# Main.net
KiCad netlist of a schematic drawn in Altium Designer
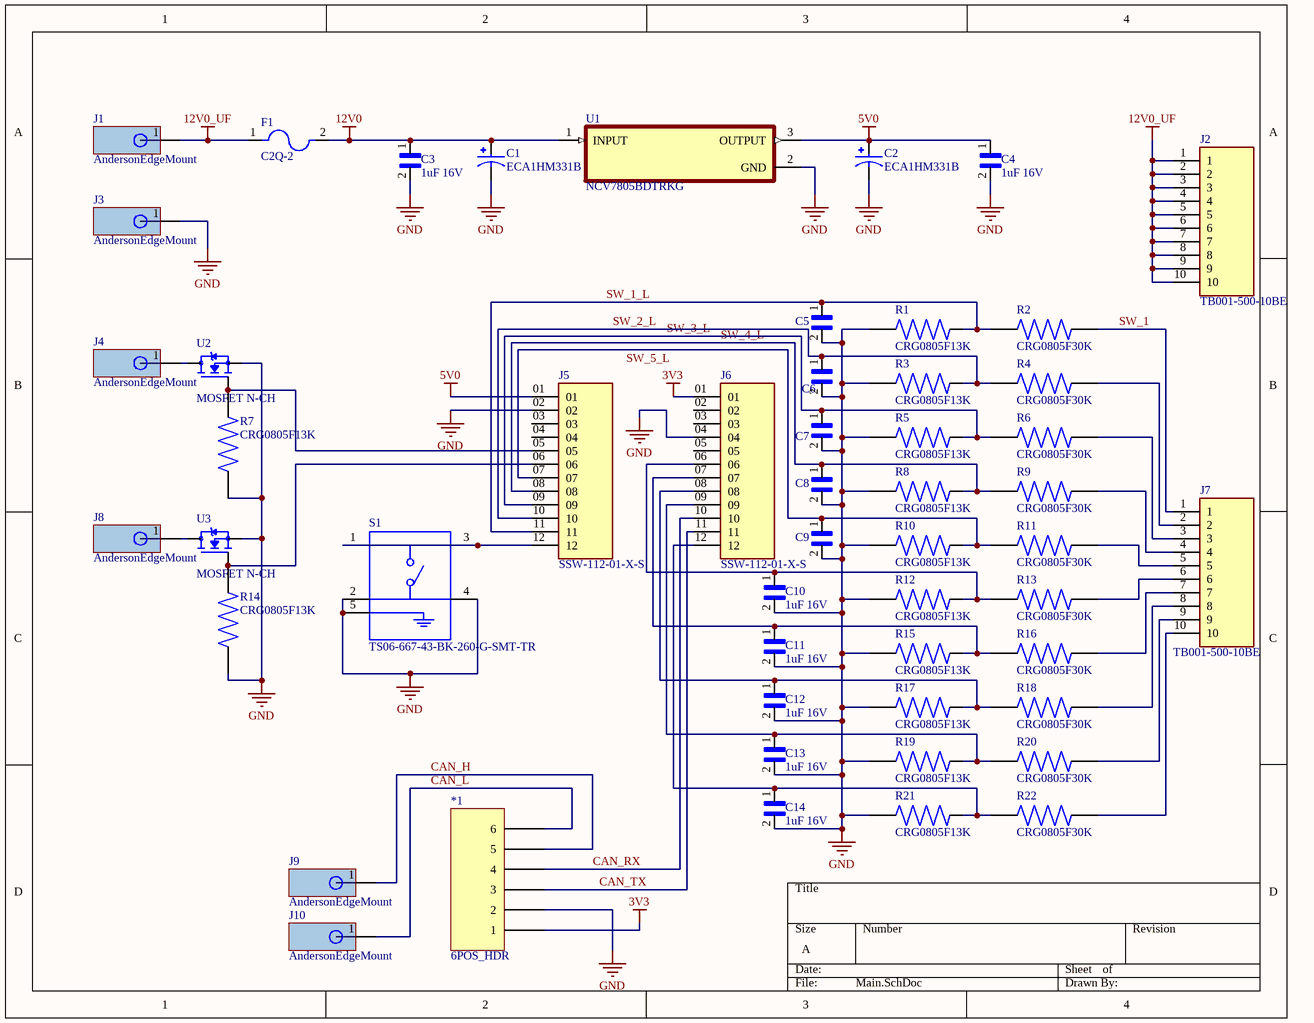
[diagram p0: Main.SchDoc]

(export (version "E")
  (design (tool "Eeschema 10.0.6"))
  (components
    (comp (ref "*1") (value "6POS_HDR") (footprint "6POS_HDR") (libsource (lib "MainLib") (part "6POS_HDR")))
    (comp (ref "C1")
      (value "ECA1HM331B")
      (footprint "CAPPRD500W60D1000H1600")
      (description "M-A")
      (fields (field (name "MF") "{'manufacturer': u'Panasonic Electronic'}"))
      (libsource (lib "SnapEDA_Library") (part "ECA1HM331B"))
    )
    (comp (ref "C2")
      (value "ECA1HM331B")
      (footprint "CAPPRD500W60D1000H1600")
      (description "M-A")
      (fields (field (name "MF") "{'manufacturer': u'Panasonic Electronic'}"))
      (libsource (lib "SnapEDA_Library") (part "ECA1HM331B"))
    )
    (comp (ref "C3")
      (value "1uF 16V")
      (footprint "CAPC2012X135N")
      (description "Cap Ceramic 1uF 16V X7R 10% Pad SMD 0805 125C T/R")
      (fields
        (field (name "MP") "CL21B105KOFNNNE")
        (field (name "MF") "{'manufacturer': u'Samsung Electro-Mechanics'}")
      )
      (libsource (lib "MCU_Lib") (part "CL21B105KOFNNNE"))
    )
    (comp (ref "C4")
      (value "1uF 16V")
      (footprint "CAPC2012X135N")
      (description "Cap Ceramic 1uF 16V X7R 10% Pad SMD 0805 125C T/R")
      (fields
        (field (name "MP") "CL21B105KOFNNNE")
        (field (name "MF") "{'manufacturer': u'Samsung Electro-Mechanics'}")
      )
      (libsource (lib "MCU_Lib") (part "CL21B105KOFNNNE"))
    )
    (comp (ref "C5")
      (value "1uF 16V")
      (footprint "CAPC2012X135N")
      (description "Cap Ceramic 1uF 16V X7R 10% Pad SMD 0805 125C T/R")
      (fields
        (field (name "MP") "CL21B105KOFNNNE")
        (field (name "MF") "{'manufacturer': u'Samsung Electro-Mechanics'}")
      )
      (libsource (lib "MCU_Lib") (part "CL21B105KOFNNNE"))
    )
    (comp (ref "C6")
      (value "1uF 16V")
      (footprint "CAPC2012X135N")
      (description "Cap Ceramic 1uF 16V X7R 10% Pad SMD 0805 125C T/R")
      (fields
        (field (name "MP") "CL21B105KOFNNNE")
        (field (name "MF") "{'manufacturer': u'Samsung Electro-Mechanics'}")
      )
      (libsource (lib "MCU_Lib") (part "CL21B105KOFNNNE"))
    )
    (comp (ref "C7")
      (value "1uF 16V")
      (footprint "CAPC2012X135N")
      (description "Cap Ceramic 1uF 16V X7R 10% Pad SMD 0805 125C T/R")
      (fields
        (field (name "MP") "CL21B105KOFNNNE")
        (field (name "MF") "{'manufacturer': u'Samsung Electro-Mechanics'}")
      )
      (libsource (lib "MCU_Lib") (part "CL21B105KOFNNNE"))
    )
    (comp (ref "C8")
      (value "1uF 16V")
      (footprint "CAPC2012X135N")
      (description "Cap Ceramic 1uF 16V X7R 10% Pad SMD 0805 125C T/R")
      (fields
        (field (name "MP") "CL21B105KOFNNNE")
        (field (name "MF") "{'manufacturer': u'Samsung Electro-Mechanics'}")
      )
      (libsource (lib "MCU_Lib") (part "CL21B105KOFNNNE"))
    )
    (comp (ref "C9")
      (value "1uF 16V")
      (footprint "CAPC2012X135N")
      (description "Cap Ceramic 1uF 16V X7R 10% Pad SMD 0805 125C T/R")
      (fields
        (field (name "MP") "CL21B105KOFNNNE")
        (field (name "MF") "{'manufacturer': u'Samsung Electro-Mechanics'}")
      )
      (libsource (lib "MCU_Lib") (part "CL21B105KOFNNNE"))
    )
    (comp (ref "C10")
      (value "1uF 16V")
      (footprint "CAPC2012X135N")
      (description "Cap Ceramic 1uF 16V X7R 10% Pad SMD 0805 125C T/R")
      (fields
        (field (name "MP") "CL21B105KOFNNNE")
        (field (name "MF") "{'manufacturer': u'Samsung Electro-Mechanics'}")
      )
      (libsource (lib "MCU_Lib") (part "CL21B105KOFNNNE"))
    )
    (comp (ref "C11")
      (value "1uF 16V")
      (footprint "CAPC2012X135N")
      (description "Cap Ceramic 1uF 16V X7R 10% Pad SMD 0805 125C T/R")
      (fields
        (field (name "MP") "CL21B105KOFNNNE")
        (field (name "MF") "{'manufacturer': u'Samsung Electro-Mechanics'}")
      )
      (libsource (lib "MCU_Lib") (part "CL21B105KOFNNNE"))
    )
    (comp (ref "C12")
      (value "1uF 16V")
      (footprint "CAPC2012X135N")
      (description "Cap Ceramic 1uF 16V X7R 10% Pad SMD 0805 125C T/R")
      (fields
        (field (name "MP") "CL21B105KOFNNNE")
        (field (name "MF") "{'manufacturer': u'Samsung Electro-Mechanics'}")
      )
      (libsource (lib "MCU_Lib") (part "CL21B105KOFNNNE"))
    )
    (comp (ref "C13")
      (value "1uF 16V")
      (footprint "CAPC2012X135N")
      (description "Cap Ceramic 1uF 16V X7R 10% Pad SMD 0805 125C T/R")
      (fields
        (field (name "MP") "CL21B105KOFNNNE")
        (field (name "MF") "{'manufacturer': u'Samsung Electro-Mechanics'}")
      )
      (libsource (lib "MCU_Lib") (part "CL21B105KOFNNNE"))
    )
    (comp (ref "C14")
      (value "1uF 16V")
      (footprint "CAPC2012X135N")
      (description "Cap Ceramic 1uF 16V X7R 10% Pad SMD 0805 125C T/R")
      (fields
        (field (name "MP") "CL21B105KOFNNNE")
        (field (name "MF") "{'manufacturer': u'Samsung Electro-Mechanics'}")
      )
      (libsource (lib "MCU_Lib") (part "CL21B105KOFNNNE"))
    )
    (comp (ref "F1")
      (value "C2Q-2")
      (footprint "FUSC1608X56N")
      (fields (field (name "MF") "{'manufacturer': u'Bel Fuse'}"))
      (libsource (lib "SnapEDA_Library") (part "C2Q-2"))
    )
    (comp (ref "J1")
      (value "AndersonEdgeMount")
      (footprint "AndersonEdgeMount")
      (description "Edge Mounted Anderson Connector")
      (libsource (lib "MainLib") (part "AndersonEdgeMount"))
    )
    (comp (ref "J2")
      (value "TB001-500-10BE")
      (footprint "CUI_TB001-500-10BE")
      (fields (field (name "MF") "{'manufacturer': u'CUI Devices'}"))
      (libsource (lib "SnapEDA_Library") (part "TB001-500-10BE"))
    )
    (comp (ref "J3")
      (value "AndersonEdgeMount")
      (footprint "AndersonEdgeMount")
      (description "Edge Mounted Anderson Connector")
      (libsource (lib "MainLib") (part "AndersonEdgeMount"))
    )
    (comp (ref "J4")
      (value "AndersonEdgeMount")
      (footprint "AndersonEdgeMount")
      (description "Edge Mounted Anderson Connector")
      (libsource (lib "MainLib") (part "AndersonEdgeMount"))
    )
    (comp (ref "J5")
      (value "SSW-112-01-X-S")
      (footprint "SAMTEC_SSW-112-01-X-S")
      (description "CONN RCPT 12POS 0.1 GOLD PCB")
      (fields (field (name "MF") "{'manufacturer': u'Samtec'}"))
      (libsource (lib "SnapEDA_Library") (part "SSW-112-01-X-S"))
    )
    (comp (ref "J6")
      (value "SSW-112-01-X-S")
      (footprint "SAMTEC_SSW-112-01-X-S")
      (description "CONN RCPT 12POS 0.1 GOLD PCB")
      (fields (field (name "MF") "{'manufacturer': u'Samtec'}"))
      (libsource (lib "SnapEDA_Library") (part "SSW-112-01-X-S"))
    )
    (comp (ref "J7")
      (value "TB001-500-10BE")
      (footprint "CUI_TB001-500-10BE")
      (fields (field (name "MF") "{'manufacturer': u'CUI Devices'}"))
      (libsource (lib "SnapEDA_Library") (part "TB001-500-10BE"))
    )
    (comp (ref "J8")
      (value "AndersonEdgeMount")
      (footprint "AndersonEdgeMount")
      (description "Edge Mounted Anderson Connector")
      (libsource (lib "MainLib") (part "AndersonEdgeMount"))
    )
    (comp (ref "J9")
      (value "AndersonEdgeMount")
      (footprint "AndersonEdgeMount")
      (description "Edge Mounted Anderson Connector")
      (libsource (lib "MainLib") (part "AndersonEdgeMount"))
    )
    (comp (ref "J10")
      (value "AndersonEdgeMount")
      (footprint "AndersonEdgeMount")
      (description "Edge Mounted Anderson Connector")
      (libsource (lib "MainLib") (part "AndersonEdgeMount"))
    )
    (comp (ref "R1")
      (value "CRG0805F13K")
      (footprint "RESC2012X65N")
      (description "CRG0805 1% 13K")
      (fields (field (name "MF") "{'manufacturer': u'TE Connectivity'}"))
      (libsource (lib "SnapEDA_Library") (part "CRG0805F13K"))
    )
    (comp (ref "R2")
      (value "CRG0805F30K")
      (footprint "RESC2012X65N")
      (description "CRG0805 1% 30K")
      (fields (field (name "MF") "{'manufacturer': u'TE Connectivity'}"))
      (libsource (lib "SnapEDA_Library") (part "CRG0805F30K"))
    )
    (comp (ref "R3")
      (value "CRG0805F13K")
      (footprint "RESC2012X65N")
      (description "CRG0805 1% 13K")
      (fields (field (name "MF") "{'manufacturer': u'TE Connectivity'}"))
      (libsource (lib "SnapEDA_Library") (part "CRG0805F13K"))
    )
    (comp (ref "R4")
      (value "CRG0805F30K")
      (footprint "RESC2012X65N")
      (description "CRG0805 1% 30K")
      (fields (field (name "MF") "{'manufacturer': u'TE Connectivity'}"))
      (libsource (lib "SnapEDA_Library") (part "CRG0805F30K"))
    )
    (comp (ref "R5")
      (value "CRG0805F13K")
      (footprint "RESC2012X65N")
      (description "CRG0805 1% 13K")
      (fields (field (name "MF") "{'manufacturer': u'TE Connectivity'}"))
      (libsource (lib "SnapEDA_Library") (part "CRG0805F13K"))
    )
    (comp (ref "R6")
      (value "CRG0805F30K")
      (footprint "RESC2012X65N")
      (description "CRG0805 1% 30K")
      (fields (field (name "MF") "{'manufacturer': u'TE Connectivity'}"))
      (libsource (lib "SnapEDA_Library") (part "CRG0805F30K"))
    )
    (comp (ref "R7")
      (value "CRG0805F13K")
      (footprint "RESC2012X65N")
      (description "CRG0805 1% 13K")
      (fields (field (name "MF") "{'manufacturer': u'TE Connectivity'}"))
      (libsource (lib "SnapEDA_Library") (part "CRG0805F13K"))
    )
    (comp (ref "R8")
      (value "CRG0805F13K")
      (footprint "RESC2012X65N")
      (description "CRG0805 1% 13K")
      (fields (field (name "MF") "{'manufacturer': u'TE Connectivity'}"))
      (libsource (lib "SnapEDA_Library") (part "CRG0805F13K"))
    )
    (comp (ref "R9")
      (value "CRG0805F30K")
      (footprint "RESC2012X65N")
      (description "CRG0805 1% 30K")
      (fields (field (name "MF") "{'manufacturer': u'TE Connectivity'}"))
      (libsource (lib "SnapEDA_Library") (part "CRG0805F30K"))
    )
    (comp (ref "R10")
      (value "CRG0805F13K")
      (footprint "RESC2012X65N")
      (description "CRG0805 1% 13K")
      (fields (field (name "MF") "{'manufacturer': u'TE Connectivity'}"))
      (libsource (lib "SnapEDA_Library") (part "CRG0805F13K"))
    )
    (comp (ref "R11")
      (value "CRG0805F30K")
      (footprint "RESC2012X65N")
      (description "CRG0805 1% 30K")
      (fields (field (name "MF") "{'manufacturer': u'TE Connectivity'}"))
      (libsource (lib "SnapEDA_Library") (part "CRG0805F30K"))
    )
    (comp (ref "R12")
      (value "CRG0805F13K")
      (footprint "RESC2012X65N")
      (description "CRG0805 1% 13K")
      (fields (field (name "MF") "{'manufacturer': u'TE Connectivity'}"))
      (libsource (lib "SnapEDA_Library") (part "CRG0805F13K"))
    )
    (comp (ref "R13")
      (value "CRG0805F30K")
      (footprint "RESC2012X65N")
      (description "CRG0805 1% 30K")
      (fields (field (name "MF") "{'manufacturer': u'TE Connectivity'}"))
      (libsource (lib "SnapEDA_Library") (part "CRG0805F30K"))
    )
    (comp (ref "R14")
      (value "CRG0805F13K")
      (footprint "RESC2012X65N")
      (description "CRG0805 1% 13K")
      (fields (field (name "MF") "{'manufacturer': u'TE Connectivity'}"))
      (libsource (lib "SnapEDA_Library") (part "CRG0805F13K"))
    )
    (comp (ref "R15")
      (value "CRG0805F13K")
      (footprint "RESC2012X65N")
      (description "CRG0805 1% 13K")
      (fields (field (name "MF") "{'manufacturer': u'TE Connectivity'}"))
      (libsource (lib "SnapEDA_Library") (part "CRG0805F13K"))
    )
    (comp (ref "R16")
      (value "CRG0805F30K")
      (footprint "RESC2012X65N")
      (description "CRG0805 1% 30K")
      (fields (field (name "MF") "{'manufacturer': u'TE Connectivity'}"))
      (libsource (lib "SnapEDA_Library") (part "CRG0805F30K"))
    )
    (comp (ref "R17")
      (value "CRG0805F13K")
      (footprint "RESC2012X65N")
      (description "CRG0805 1% 13K")
      (fields (field (name "MF") "{'manufacturer': u'TE Connectivity'}"))
      (libsource (lib "SnapEDA_Library") (part "CRG0805F13K"))
    )
    (comp (ref "R18")
      (value "CRG0805F30K")
      (footprint "RESC2012X65N")
      (description "CRG0805 1% 30K")
      (fields (field (name "MF") "{'manufacturer': u'TE Connectivity'}"))
      (libsource (lib "SnapEDA_Library") (part "CRG0805F30K"))
    )
    (comp (ref "R19")
      (value "CRG0805F13K")
      (footprint "RESC2012X65N")
      (description "CRG0805 1% 13K")
      (fields (field (name "MF") "{'manufacturer': u'TE Connectivity'}"))
      (libsource (lib "SnapEDA_Library") (part "CRG0805F13K"))
    )
    (comp (ref "R20")
      (value "CRG0805F30K")
      (footprint "RESC2012X65N")
      (description "CRG0805 1% 30K")
      (fields (field (name "MF") "{'manufacturer': u'TE Connectivity'}"))
      (libsource (lib "SnapEDA_Library") (part "CRG0805F30K"))
    )
    (comp (ref "R21")
      (value "CRG0805F13K")
      (footprint "RESC2012X65N")
      (description "CRG0805 1% 13K")
      (fields (field (name "MF") "{'manufacturer': u'TE Connectivity'}"))
      (libsource (lib "SnapEDA_Library") (part "CRG0805F13K"))
    )
    (comp (ref "R22")
      (value "CRG0805F30K")
      (footprint "RESC2012X65N")
      (description "CRG0805 1% 30K")
      (fields (field (name "MF") "{'manufacturer': u'TE Connectivity'}"))
      (libsource (lib "SnapEDA_Library") (part "CRG0805F30K"))
    )
    (comp (ref "S1")
      (value "TS06-667-43-BK-260-G-SMT-TR")
      (footprint "SW_TS06-667-43-BK-260-G-SMT-TR")
      (fields (field (name "MF") "{'manufacturer': u'CUI Devices'}"))
      (libsource (lib "SnapEDA_Library") (part "TS06-667-43-BK-260-G-SMT-TR"))
    )
    (comp (ref "U1")
      (value "NCV7805BDTRKG")
      (footprint "DPAK229P990X238-4N")
      (fields (field (name "MF") "{'manufacturer': u'ON Semiconductor'}"))
      (libsource (lib "SnapEDA_Library") (part "NCV7805BDTRKG"))
    )
    (comp (ref "U2")
      (value "MOSFET N-CH")
      (footprint "ZXMN6A09GTA")
      (libsource (lib "MainLib") (part "ZXMN6A09GTA"))
    )
    (comp (ref "U3")
      (value "MOSFET N-CH")
      (footprint "ZXMN6A09GTA")
      (libsource (lib "MainLib") (part "ZXMN6A09GTA"))
    )
  )
  (nets
    (net (code "1") (name "/CAN_H") (class "Default")
      (node (ref "*1") (pin "5") (pinfunction "5_5") (pintype "passive"))
      (node (ref "J9") (pin "1") (pinfunction "1_1") (pintype "passive"))
    )
    (net (code "2") (name "/CAN_L") (class "Default")
      (node (ref "*1") (pin "6") (pinfunction "6_6") (pintype "passive"))
      (node (ref "J10") (pin "1") (pinfunction "1_1") (pintype "passive"))
    )
    (net (code "3") (name "/CAN_RX") (class "Default")
      (node (ref "*1") (pin "4") (pinfunction "4_4") (pintype "passive"))
      (node (ref "J6") (pin "10") (pinfunction "10_10") (pintype "passive"))
    )
    (net (code "4") (name "/CAN_TX") (class "Default")
      (node (ref "*1") (pin "3") (pinfunction "3_3") (pintype "passive"))
      (node (ref "J6") (pin "11") (pinfunction "11_11") (pintype "passive"))
    )
    (net (code "5") (name "/SW_1") (class "Default")
      (node (ref "J7") (pin "1") (pinfunction "1_1") (pintype "passive"))
      (node (ref "R2") (pin "2") (pinfunction "2_2") (pintype "passive"))
    )
    (net (code "6") (name "/SW_1_L") (class "Default")
      (node (ref "C5") (pin "1") (pinfunction "1_1") (pintype "passive"))
      (node (ref "J5") (pin "11") (pinfunction "11_11") (pintype "passive"))
      (node (ref "R1") (pin "1") (pinfunction "1_1") (pintype "passive"))
      (node (ref "R2") (pin "1") (pinfunction "1_1") (pintype "passive"))
    )
    (net (code "7") (name "/SW_2_L") (class "Default")
      (node (ref "C6") (pin "1") (pinfunction "1_1") (pintype "passive"))
      (node (ref "J5") (pin "10") (pinfunction "10_10") (pintype "passive"))
      (node (ref "R3") (pin "1") (pinfunction "1_1") (pintype "passive"))
      (node (ref "R4") (pin "1") (pinfunction "1_1") (pintype "passive"))
    )
    (net (code "8") (name "/SW_3_L") (class "Default")
      (node (ref "C7") (pin "1") (pinfunction "1_1") (pintype "passive"))
      (node (ref "J5") (pin "09") (pinfunction "09_09") (pintype "passive"))
      (node (ref "R5") (pin "1") (pinfunction "1_1") (pintype "passive"))
      (node (ref "R6") (pin "1") (pinfunction "1_1") (pintype "passive"))
    )
    (net (code "9") (name "/SW_4_L") (class "Default")
      (node (ref "C8") (pin "1") (pinfunction "1_1") (pintype "passive"))
      (node (ref "J5") (pin "08") (pinfunction "08_08") (pintype "passive"))
      (node (ref "R8") (pin "1") (pinfunction "1_1") (pintype "passive"))
      (node (ref "R9") (pin "1") (pinfunction "1_1") (pintype "passive"))
    )
    (net (code "10") (name "/SW_5_L") (class "Default")
      (node (ref "C9") (pin "1") (pinfunction "1_1") (pintype "passive"))
      (node (ref "J5") (pin "07") (pinfunction "07_07") (pintype "passive"))
      (node (ref "R10") (pin "1") (pinfunction "1_1") (pintype "passive"))
      (node (ref "R11") (pin "1") (pinfunction "1_1") (pintype "passive"))
    )
    (net (code "11") (name "3V3") (class "Default")
      (node (ref "*1") (pin "1") (pinfunction "1_1") (pintype "passive"))
      (node (ref "J6") (pin "01") (pinfunction "01_01") (pintype "passive"))
    )
    (net (code "12") (name "5V0") (class "Default")
      (node (ref "C2") (pin "P") (pinfunction "P_P") (pintype "passive"))
      (node (ref "C4") (pin "1") (pinfunction "1_1") (pintype "passive"))
      (node (ref "J5") (pin "01") (pinfunction "01_01") (pintype "passive"))
      (node (ref "U1") (pin "3") (pinfunction "OUTPUT_3") (pintype "output"))
    )
    (net (code "13") (name "12V0") (class "Default")
      (node (ref "C1") (pin "P") (pinfunction "P_P") (pintype "passive"))
      (node (ref "C3") (pin "1") (pinfunction "1_1") (pintype "passive"))
      (node (ref "F1") (pin "2") (pinfunction "2_2") (pintype "passive"))
      (node (ref "U1") (pin "1") (pinfunction "INPUT_1") (pintype "input"))
    )
    (net (code "14") (name "12V0_UF") (class "Default")
      (node (ref "F1") (pin "1") (pinfunction "1_1") (pintype "passive"))
      (node (ref "J1") (pin "1") (pinfunction "1_1") (pintype "passive"))
      (node (ref "J2") (pin "1") (pinfunction "1_1") (pintype "passive"))
      (node (ref "J2") (pin "10") (pinfunction "10_10") (pintype "passive"))
      (node (ref "J2") (pin "2") (pinfunction "2_2") (pintype "passive"))
      (node (ref "J2") (pin "3") (pinfunction "3_3") (pintype "passive"))
      (node (ref "J2") (pin "4") (pinfunction "4_4") (pintype "passive"))
      (node (ref "J2") (pin "5") (pinfunction "5_5") (pintype "passive"))
      (node (ref "J2") (pin "6") (pinfunction "6_6") (pintype "passive"))
      (node (ref "J2") (pin "7") (pinfunction "7_7") (pintype "passive"))
      (node (ref "J2") (pin "8") (pinfunction "8_8") (pintype "passive"))
      (node (ref "J2") (pin "9") (pinfunction "9_9") (pintype "passive"))
    )
    (net (code "15") (name "GND") (class "Default")
      (node (ref "*1") (pin "2") (pinfunction "2_2") (pintype "passive"))
      (node (ref "C1") (pin "N") (pinfunction "N_N") (pintype "passive"))
      (node (ref "C10") (pin "2") (pinfunction "2_2") (pintype "passive"))
      (node (ref "C11") (pin "2") (pinfunction "2_2") (pintype "passive"))
      (node (ref "C12") (pin "2") (pinfunction "2_2") (pintype "passive"))
      (node (ref "C13") (pin "2") (pinfunction "2_2") (pintype "passive"))
      (node (ref "C14") (pin "2") (pinfunction "2_2") (pintype "passive"))
      (node (ref "C2") (pin "N") (pinfunction "N_N") (pintype "passive"))
      (node (ref "C3") (pin "2") (pinfunction "2_2") (pintype "passive"))
      (node (ref "C4") (pin "2") (pinfunction "2_2") (pintype "passive"))
      (node (ref "C5") (pin "2") (pinfunction "2_2") (pintype "passive"))
      (node (ref "C6") (pin "2") (pinfunction "2_2") (pintype "passive"))
      (node (ref "C7") (pin "2") (pinfunction "2_2") (pintype "passive"))
      (node (ref "C8") (pin "2") (pinfunction "2_2") (pintype "passive"))
      (node (ref "C9") (pin "2") (pinfunction "2_2") (pintype "passive"))
      (node (ref "J3") (pin "1") (pinfunction "1_1") (pintype "passive"))
      (node (ref "J5") (pin "02") (pinfunction "02_02") (pintype "passive"))
      (node (ref "J6") (pin "04") (pinfunction "04_04") (pintype "passive"))
      (node (ref "R1") (pin "2") (pinfunction "2_2") (pintype "passive"))
      (node (ref "R10") (pin "2") (pinfunction "2_2") (pintype "passive"))
      (node (ref "R12") (pin "2") (pinfunction "2_2") (pintype "passive"))
      (node (ref "R14") (pin "1") (pinfunction "1_1") (pintype "passive"))
      (node (ref "R15") (pin "2") (pinfunction "2_2") (pintype "passive"))
      (node (ref "R17") (pin "2") (pinfunction "2_2") (pintype "passive"))
      (node (ref "R19") (pin "2") (pinfunction "2_2") (pintype "passive"))
      (node (ref "R21") (pin "2") (pinfunction "2_2") (pintype "passive"))
      (node (ref "R3") (pin "2") (pinfunction "2_2") (pintype "passive"))
      (node (ref "R5") (pin "2") (pinfunction "2_2") (pintype "passive"))
      (node (ref "R7") (pin "1") (pinfunction "1_1") (pintype "passive"))
      (node (ref "R8") (pin "2") (pinfunction "2_2") (pintype "passive"))
      (node (ref "S1") (pin "2") (pinfunction "2_2") (pintype "passive"))
      (node (ref "S1") (pin "4") (pinfunction "4_4") (pintype "passive"))
      (node (ref "S1") (pin "5") (pinfunction "5_5") (pintype "passive"))
      (node (ref "U1") (pin "2") (pinfunction "GND_2") (pintype "power_in"))
      (node (ref "U2") (pin "3") (pinfunction "3_3") (pintype "passive"))
      (node (ref "U3") (pin "3") (pinfunction "3_3") (pintype "passive"))
    )
    (net (code "16") (name "Net-(C10-Pad1)") (class "Default")
      (node (ref "C10") (pin "1") (pinfunction "1_1") (pintype "passive"))
      (node (ref "J6") (pin "06") (pinfunction "06_06") (pintype "passive"))
      (node (ref "R12") (pin "1") (pinfunction "1_1") (pintype "passive"))
      (node (ref "R13") (pin "1") (pinfunction "1_1") (pintype "passive"))
    )
    (net (code "17") (name "Net-(C11-Pad1)") (class "Default")
      (node (ref "C11") (pin "1") (pinfunction "1_1") (pintype "passive"))
      (node (ref "J6") (pin "07") (pinfunction "07_07") (pintype "passive"))
      (node (ref "R15") (pin "1") (pinfunction "1_1") (pintype "passive"))
      (node (ref "R16") (pin "1") (pinfunction "1_1") (pintype "passive"))
    )
    (net (code "18") (name "Net-(C12-Pad1)") (class "Default")
      (node (ref "C12") (pin "1") (pinfunction "1_1") (pintype "passive"))
      (node (ref "J6") (pin "08") (pinfunction "08_08") (pintype "passive"))
      (node (ref "R17") (pin "1") (pinfunction "1_1") (pintype "passive"))
      (node (ref "R18") (pin "1") (pinfunction "1_1") (pintype "passive"))
    )
    (net (code "19") (name "Net-(C13-Pad1)") (class "Default")
      (node (ref "C13") (pin "1") (pinfunction "1_1") (pintype "passive"))
      (node (ref "J6") (pin "09") (pinfunction "09_09") (pintype "passive"))
      (node (ref "R19") (pin "1") (pinfunction "1_1") (pintype "passive"))
      (node (ref "R20") (pin "1") (pinfunction "1_1") (pintype "passive"))
    )
    (net (code "20") (name "Net-(C14-Pad1)") (class "Default")
      (node (ref "C14") (pin "1") (pinfunction "1_1") (pintype "passive"))
      (node (ref "J6") (pin "12") (pinfunction "12_12") (pintype "passive"))
      (node (ref "R21") (pin "1") (pinfunction "1_1") (pintype "passive"))
      (node (ref "R22") (pin "1") (pinfunction "1_1") (pintype "passive"))
    )
    (net (code "21") (name "Net-(J4-Pad1)") (class "Default")
      (node (ref "J4") (pin "1") (pinfunction "1_1") (pintype "passive"))
      (node (ref "U2") (pin "2") (pinfunction "2_2") (pintype "passive"))
    )
    (net (code "22") (name "Net-(J5-Pad05)") (class "Default")
      (node (ref "J5") (pin "05") (pinfunction "05_05") (pintype "passive"))
      (node (ref "R7") (pin "2") (pinfunction "2_2") (pintype "passive"))
      (node (ref "U2") (pin "1") (pinfunction "1_1") (pintype "passive"))
    )
    (net (code "23") (name "Net-(J5-Pad06)") (class "Default")
      (node (ref "J5") (pin "06") (pinfunction "06_06") (pintype "passive"))
      (node (ref "R14") (pin "2") (pinfunction "2_2") (pintype "passive"))
      (node (ref "U3") (pin "1") (pinfunction "1_1") (pintype "passive"))
    )
    (net (code "24") (name "Net-(J5-Pad12)") (class "Default")
      (node (ref "J5") (pin "12") (pinfunction "12_12") (pintype "passive"))
      (node (ref "S1") (pin "1") (pinfunction "1_1") (pintype "passive"))
      (node (ref "S1") (pin "3") (pinfunction "3_3") (pintype "passive"))
    )
    (net (code "25") (name "Net-(J7-Pad2)") (class "Default")
      (node (ref "J7") (pin "2") (pinfunction "2_2") (pintype "passive"))
      (node (ref "R4") (pin "2") (pinfunction "2_2") (pintype "passive"))
    )
    (net (code "26") (name "Net-(J7-Pad3)") (class "Default")
      (node (ref "J7") (pin "3") (pinfunction "3_3") (pintype "passive"))
      (node (ref "R6") (pin "2") (pinfunction "2_2") (pintype "passive"))
    )
    (net (code "27") (name "Net-(J7-Pad4)") (class "Default")
      (node (ref "J7") (pin "4") (pinfunction "4_4") (pintype "passive"))
      (node (ref "R9") (pin "2") (pinfunction "2_2") (pintype "passive"))
    )
    (net (code "28") (name "Net-(J7-Pad5)") (class "Default")
      (node (ref "J7") (pin "5") (pinfunction "5_5") (pintype "passive"))
      (node (ref "R11") (pin "2") (pinfunction "2_2") (pintype "passive"))
    )
    (net (code "29") (name "Net-(J7-Pad6)") (class "Default")
      (node (ref "J7") (pin "6") (pinfunction "6_6") (pintype "passive"))
      (node (ref "R13") (pin "2") (pinfunction "2_2") (pintype "passive"))
    )
    (net (code "30") (name "Net-(J7-Pad7)") (class "Default")
      (node (ref "J7") (pin "7") (pinfunction "7_7") (pintype "passive"))
      (node (ref "R16") (pin "2") (pinfunction "2_2") (pintype "passive"))
    )
    (net (code "31") (name "Net-(J7-Pad8)") (class "Default")
      (node (ref "J7") (pin "8") (pinfunction "8_8") (pintype "passive"))
      (node (ref "R18") (pin "2") (pinfunction "2_2") (pintype "passive"))
    )
    (net (code "32") (name "Net-(J7-Pad9)") (class "Default")
      (node (ref "J7") (pin "9") (pinfunction "9_9") (pintype "passive"))
      (node (ref "R20") (pin "2") (pinfunction "2_2") (pintype "passive"))
    )
    (net (code "33") (name "Net-(J7-Pad10)") (class "Default")
      (node (ref "J7") (pin "10") (pinfunction "10_10") (pintype "passive"))
      (node (ref "R22") (pin "2") (pinfunction "2_2") (pintype "passive"))
    )
    (net (code "34") (name "Net-(J8-Pad1)") (class "Default")
      (node (ref "J8") (pin "1") (pinfunction "1_1") (pintype "passive"))
      (node (ref "U3") (pin "2") (pinfunction "2_2") (pintype "passive"))
    )
    (net (code "35") (name "unconnected-(J5-Pad03)") (class "Default")
      (node (ref "J5") (pin "03") (pinfunction "03_03") (pintype "passive"))
    )
    (net (code "36") (name "unconnected-(J5-Pad04)") (class "Default")
      (node (ref "J5") (pin "04") (pinfunction "04_04") (pintype "passive"))
    )
    (net (code "37") (name "unconnected-(J6-Pad02)") (class "Default")
      (node (ref "J6") (pin "02") (pinfunction "02_02") (pintype "passive"))
    )
    (net (code "38") (name "unconnected-(J6-Pad03)") (class "Default")
      (node (ref "J6") (pin "03") (pinfunction "03_03") (pintype "passive"))
    )
    (net (code "39") (name "unconnected-(J6-Pad05)") (class "Default")
      (node (ref "J6") (pin "05") (pinfunction "05_05") (pintype "passive"))
    )
  )
)
